# gdoor.net
KiCad netlist of a schematic drawn in EAGLE
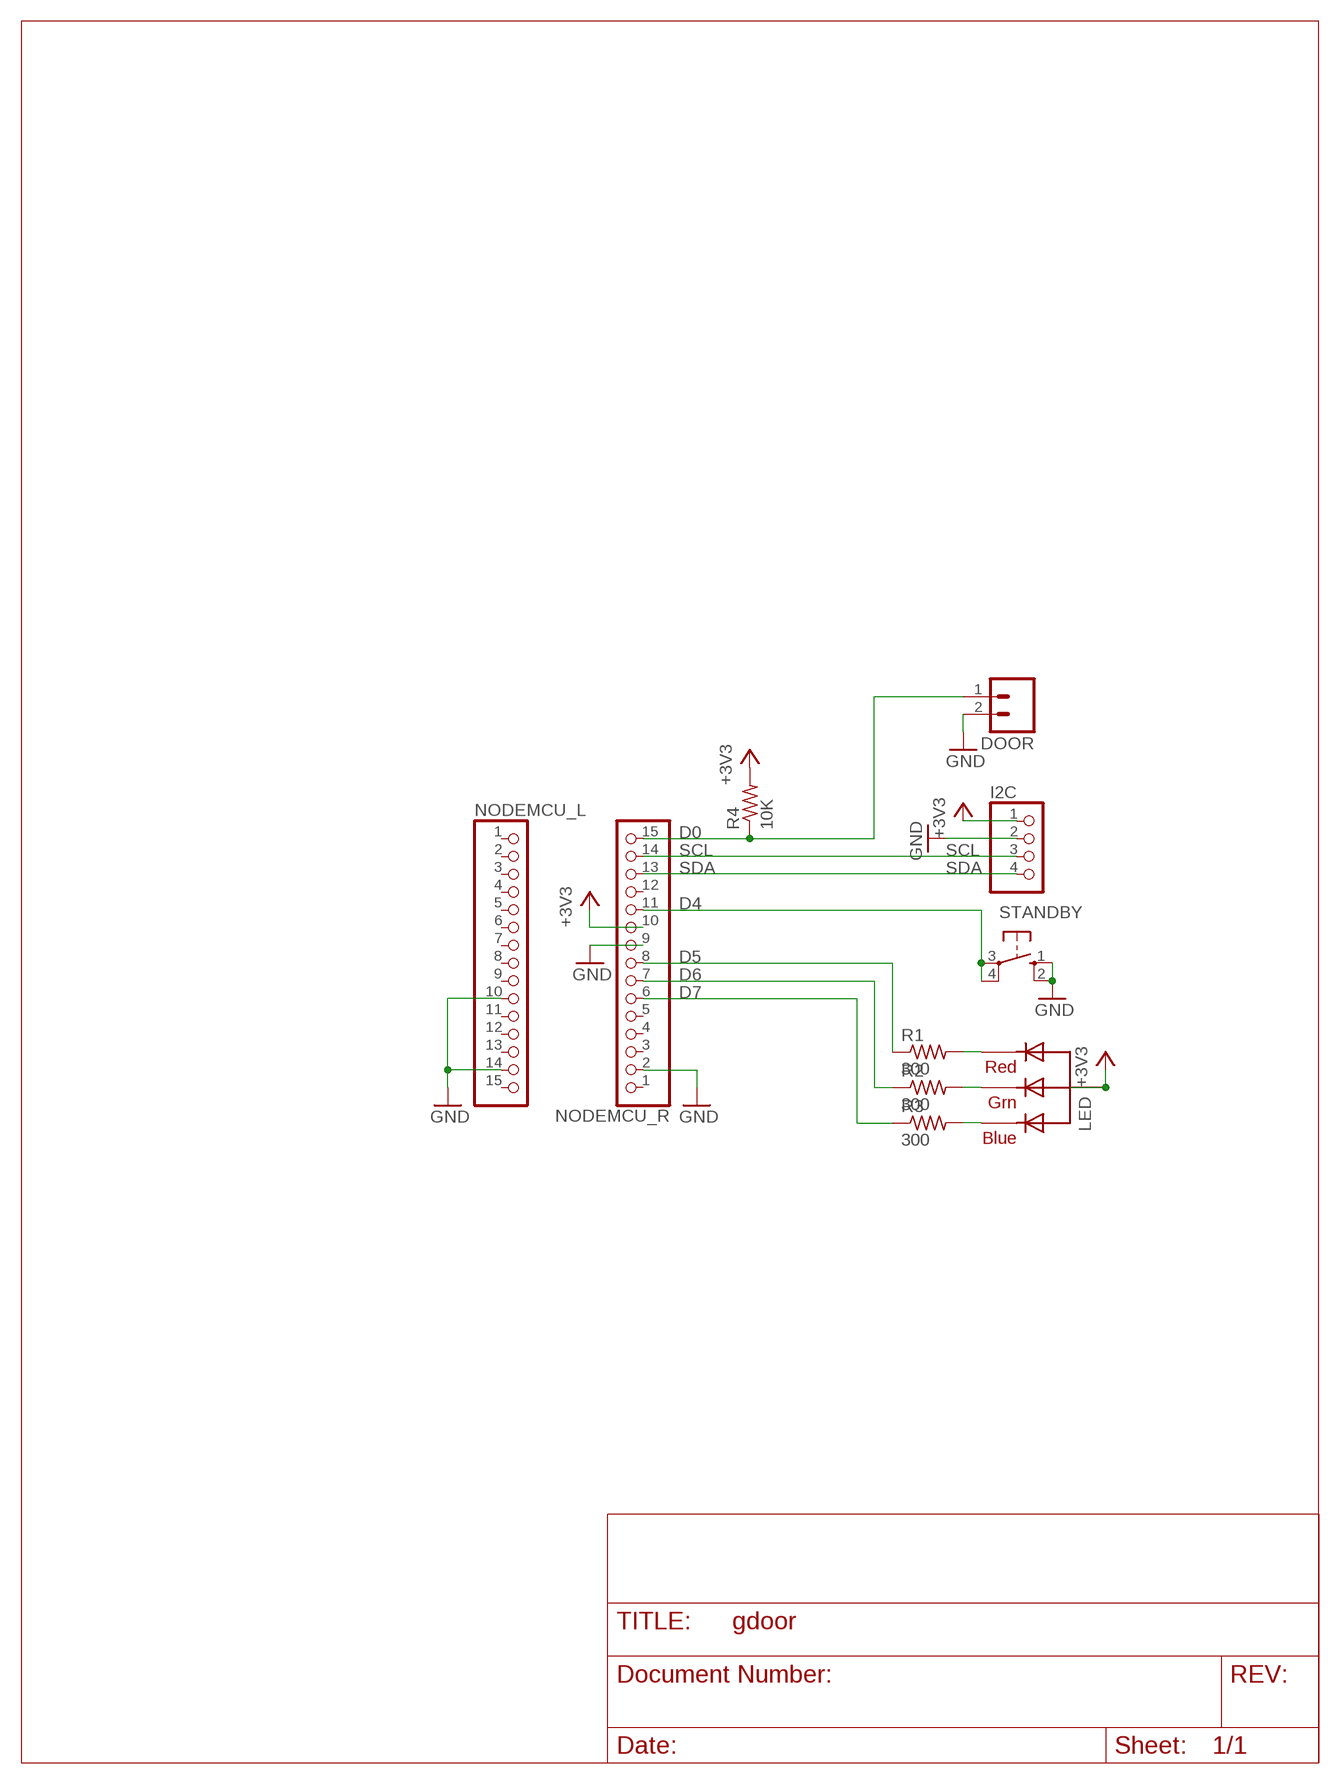
[diagram p0: schematic, sheet 1]

(export (version "E")
  (design (tool "Eeschema 10.0.6"))
  (components
    (comp (ref "DOOR")
      (value "M025MM")
      (footprint "eagle-import:SCREWTERMINAL-5MM-2")
      (libsource (lib "eagle-import") (part "M025MM"))
    )
    (comp (ref "I2C")
      (value "PINHD-1X4")
      (footprint "eagle-import:1X04")
      (libsource (lib "eagle-import") (part "PINHD-1X4"))
    )
    (comp (ref "LED")
      (value "RGBLED_CA-5MM")
      (footprint "eagle-import:LED5MMRGB")
      (libsource (lib "eagle-import") (part "RGBLED_CA-5MM"))
    )
    (comp (ref "NODEMCU_L")
      (value "PINHD-1X15")
      (footprint "eagle-import:1X15")
      (libsource (lib "eagle-import") (part "PINHD-1X15"))
    )
    (comp (ref "NODEMCU_R")
      (value "PINHD-1X15")
      (footprint "eagle-import:1X15")
      (libsource (lib "eagle-import") (part "PINHD-1X15"))
    )
    (comp (ref "R1")
      (value "300")
      (footprint "eagle-import:0207_10")
      (libsource (lib "eagle-import") (part "R-US_0207/10"))
    )
    (comp (ref "R2")
      (value "300")
      (footprint "eagle-import:0207_10")
      (libsource (lib "eagle-import") (part "R-US_0207/10"))
    )
    (comp (ref "R3")
      (value "300")
      (footprint "eagle-import:0207_10")
      (libsource (lib "eagle-import") (part "R-US_0207/10"))
    )
    (comp (ref "R4")
      (value "10K")
      (footprint "eagle-import:0207_10")
      (libsource (lib "eagle-import") (part "R-US_0207/10"))
    )
    (comp (ref "STANDBY")
      (value "10-XX")
      (footprint "eagle-import:B3F-10XX")
      (fields (field (name "MPN") "B3F-1000"))
      (libsource (lib "eagle-import") (part "10-XX"))
    )
  )
  (nets
    (net (code "1") (name "+3V3") (class "Default")
      (node (ref "I2C") (pin "1") (pinfunction "1_1") (pintype "passive"))
      (node (ref "LED") (pin "2") (pinfunction "VCC_2") (pintype "bidirectional"))
      (node (ref "NODEMCU_R") (pin "10") (pinfunction "10_10") (pintype "passive"))
      (node (ref "R4") (pin "2") (pinfunction "2_2") (pintype "passive"))
    )
    (net (code "2") (name "/D0") (class "Default")
      (node (ref "DOOR") (pin "1") (pinfunction "1_1") (pintype "passive"))
      (node (ref "NODEMCU_R") (pin "15") (pinfunction "15_15") (pintype "passive"))
      (node (ref "R4") (pin "1") (pinfunction "1_1") (pintype "passive"))
    )
    (net (code "3") (name "/D4") (class "Default")
      (node (ref "NODEMCU_R") (pin "11") (pinfunction "11_11") (pintype "passive"))
      (node (ref "STANDBY") (pin "3") (pinfunction "P_3") (pintype "passive"))
      (node (ref "STANDBY") (pin "4") (pinfunction "P1_4") (pintype "passive"))
    )
    (net (code "4") (name "/D5") (class "Default")
      (node (ref "NODEMCU_R") (pin "8") (pinfunction "8_8") (pintype "passive"))
      (node (ref "R1") (pin "1") (pinfunction "1_1") (pintype "passive"))
    )
    (net (code "5") (name "/D6") (class "Default")
      (node (ref "NODEMCU_R") (pin "7") (pinfunction "7_7") (pintype "passive"))
      (node (ref "R2") (pin "1") (pinfunction "1_1") (pintype "passive"))
    )
    (net (code "6") (name "/D7") (class "Default")
      (node (ref "NODEMCU_R") (pin "6") (pinfunction "6_6") (pintype "passive"))
      (node (ref "R3") (pin "1") (pinfunction "1_1") (pintype "passive"))
    )
    (net (code "7") (name "/SCL") (class "Default")
      (node (ref "I2C") (pin "3") (pinfunction "3_3") (pintype "passive"))
      (node (ref "NODEMCU_R") (pin "14") (pinfunction "14_14") (pintype "passive"))
    )
    (net (code "8") (name "/SDA") (class "Default")
      (node (ref "I2C") (pin "4") (pinfunction "4_4") (pintype "passive"))
      (node (ref "NODEMCU_R") (pin "13") (pinfunction "13_13") (pintype "passive"))
    )
    (net (code "9") (name "GND") (class "Default")
      (node (ref "DOOR") (pin "2") (pinfunction "2_2") (pintype "passive"))
      (node (ref "I2C") (pin "2") (pinfunction "2_2") (pintype "passive"))
      (node (ref "NODEMCU_L") (pin "10") (pinfunction "10_10") (pintype "passive"))
      (node (ref "NODEMCU_L") (pin "14") (pinfunction "14_14") (pintype "passive"))
      (node (ref "NODEMCU_R") (pin "2") (pinfunction "2_2") (pintype "passive"))
      (node (ref "NODEMCU_R") (pin "9") (pinfunction "9_9") (pintype "passive"))
      (node (ref "STANDBY") (pin "1") (pinfunction "S_1") (pintype "passive"))
      (node (ref "STANDBY") (pin "2") (pinfunction "S1_2") (pintype "passive"))
    )
    (net (code "10") (name "Net-(LED-BLUE)") (class "Default")
      (node (ref "LED") (pin "4") (pinfunction "BLUE_4") (pintype "bidirectional"))
      (node (ref "R3") (pin "2") (pinfunction "2_2") (pintype "passive"))
    )
    (net (code "11") (name "Net-(LED-GREEN)") (class "Default")
      (node (ref "LED") (pin "3") (pinfunction "GREEN_3") (pintype "bidirectional"))
      (node (ref "R2") (pin "2") (pinfunction "2_2") (pintype "passive"))
    )
    (net (code "12") (name "Net-(LED-RED)") (class "Default")
      (node (ref "LED") (pin "1") (pinfunction "RED_1") (pintype "bidirectional"))
      (node (ref "R1") (pin "2") (pinfunction "2_2") (pintype "passive"))
    )
    (net (code "13") (name "unconnected-(NODEMCU_L-Pad1)") (class "Default")
      (node (ref "NODEMCU_L") (pin "1") (pinfunction "1_1") (pintype "passive"))
    )
    (net (code "14") (name "unconnected-(NODEMCU_L-Pad2)") (class "Default")
      (node (ref "NODEMCU_L") (pin "2") (pinfunction "2_2") (pintype "passive"))
    )
    (net (code "15") (name "unconnected-(NODEMCU_L-Pad3)") (class "Default")
      (node (ref "NODEMCU_L") (pin "3") (pinfunction "3_3") (pintype "passive"))
    )
    (net (code "16") (name "unconnected-(NODEMCU_L-Pad4)") (class "Default")
      (node (ref "NODEMCU_L") (pin "4") (pinfunction "4_4") (pintype "passive"))
    )
    (net (code "17") (name "unconnected-(NODEMCU_L-Pad5)") (class "Default")
      (node (ref "NODEMCU_L") (pin "5") (pinfunction "5_5") (pintype "passive"))
    )
    (net (code "18") (name "unconnected-(NODEMCU_L-Pad6)") (class "Default")
      (node (ref "NODEMCU_L") (pin "6") (pinfunction "6_6") (pintype "passive"))
    )
    (net (code "19") (name "unconnected-(NODEMCU_L-Pad7)") (class "Default")
      (node (ref "NODEMCU_L") (pin "7") (pinfunction "7_7") (pintype "passive"))
    )
    (net (code "20") (name "unconnected-(NODEMCU_L-Pad8)") (class "Default")
      (node (ref "NODEMCU_L") (pin "8") (pinfunction "8_8") (pintype "passive"))
    )
    (net (code "21") (name "unconnected-(NODEMCU_L-Pad9)") (class "Default")
      (node (ref "NODEMCU_L") (pin "9") (pinfunction "9_9") (pintype "passive"))
    )
    (net (code "22") (name "unconnected-(NODEMCU_L-Pad11)") (class "Default")
      (node (ref "NODEMCU_L") (pin "11") (pinfunction "11_11") (pintype "passive"))
    )
    (net (code "23") (name "unconnected-(NODEMCU_L-Pad12)") (class "Default")
      (node (ref "NODEMCU_L") (pin "12") (pinfunction "12_12") (pintype "passive"))
    )
    (net (code "24") (name "unconnected-(NODEMCU_L-Pad13)") (class "Default")
      (node (ref "NODEMCU_L") (pin "13") (pinfunction "13_13") (pintype "passive"))
    )
    (net (code "25") (name "unconnected-(NODEMCU_L-Pad15)") (class "Default")
      (node (ref "NODEMCU_L") (pin "15") (pinfunction "15_15") (pintype "passive"))
    )
    (net (code "26") (name "unconnected-(NODEMCU_R-Pad1)") (class "Default")
      (node (ref "NODEMCU_R") (pin "1") (pinfunction "1_1") (pintype "passive"))
    )
    (net (code "27") (name "unconnected-(NODEMCU_R-Pad3)") (class "Default")
      (node (ref "NODEMCU_R") (pin "3") (pinfunction "3_3") (pintype "passive"))
    )
    (net (code "28") (name "unconnected-(NODEMCU_R-Pad4)") (class "Default")
      (node (ref "NODEMCU_R") (pin "4") (pinfunction "4_4") (pintype "passive"))
    )
    (net (code "29") (name "unconnected-(NODEMCU_R-Pad5)") (class "Default")
      (node (ref "NODEMCU_R") (pin "5") (pinfunction "5_5") (pintype "passive"))
    )
    (net (code "30") (name "unconnected-(NODEMCU_R-Pad12)") (class "Default")
      (node (ref "NODEMCU_R") (pin "12") (pinfunction "12_12") (pintype "passive"))
    )
  )
)
